# Actual.net
KiCad netlist of a schematic drawn in Altium Designer
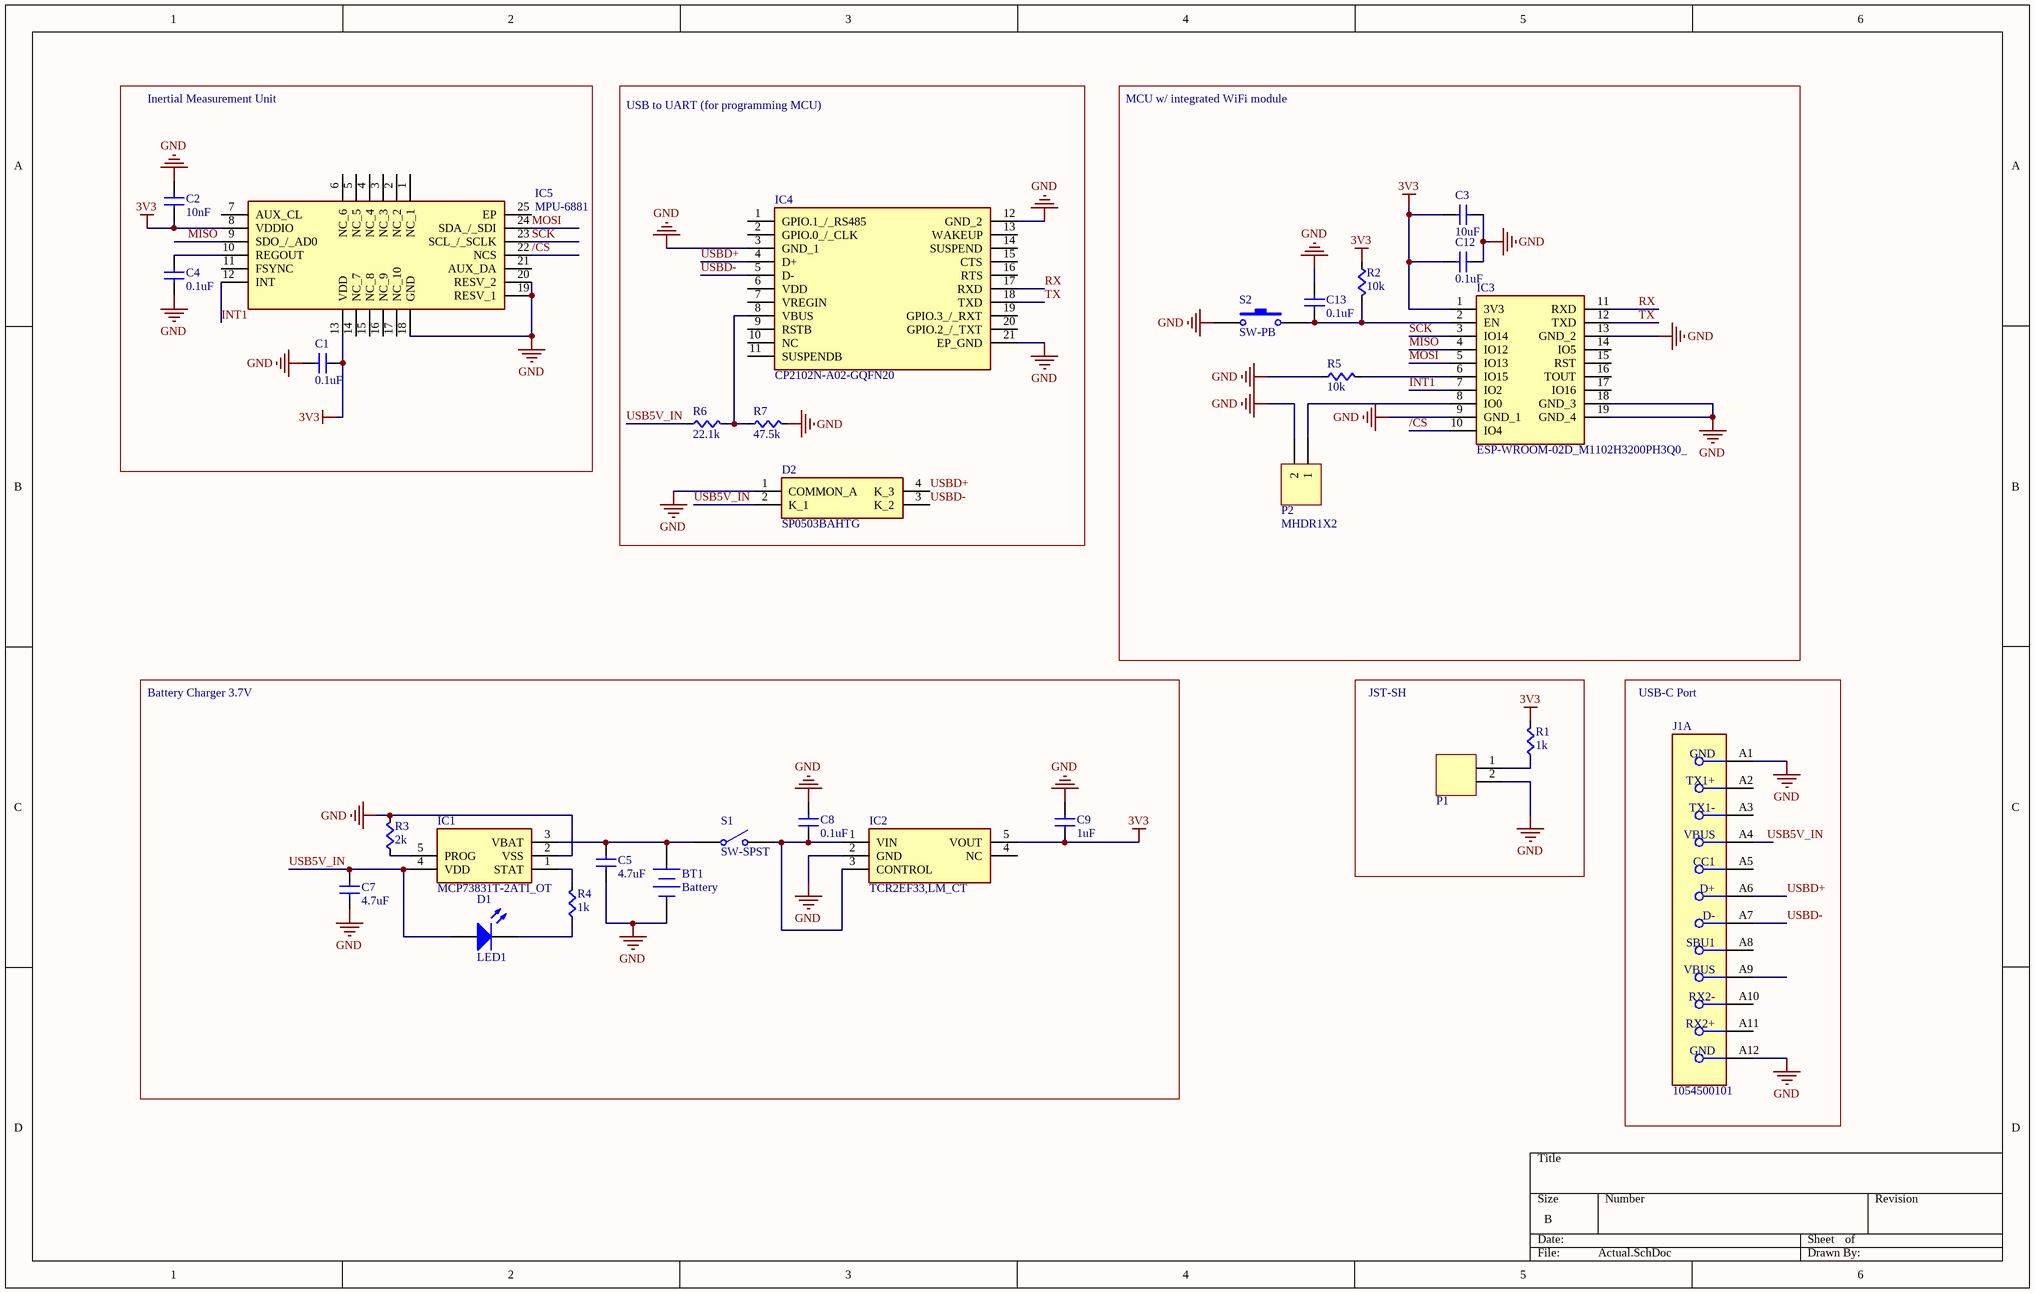
[diagram p0: Actual.SchDoc]

(export (version "E")
  (design (tool "Eeschema 10.0.6"))
  (components
    (comp (ref "BT1")
      (value "Battery")
      (footprint "BAT-2")
      (description "Multicell Battery")
      (fields (field (name "PUBLISHER") "Altium Limited"))
      (libsource (lib "Miscellaneous Devices") (part "Battery"))
    )
    (comp (ref "C1")
      (value "0.1uF")
      (footprint "CAPC0603")
      (fields (field (name "Comment") "Cap"))
      (libsource (lib "Passives") (part "Cap"))
    )
    (comp (ref "C2")
      (value "10nF")
      (footprint "CAPC0603")
      (fields (field (name "Comment") "Cap"))
      (libsource (lib "Passives") (part "Cap"))
    )
    (comp (ref "C3")
      (value "10uF")
      (footprint "CAPC0603")
      (fields (field (name "Comment") "Cap"))
      (libsource (lib "Passives") (part "Cap"))
    )
    (comp (ref "C4")
      (value "0.1uF")
      (footprint "CAPC0603")
      (fields (field (name "Comment") "Cap"))
      (libsource (lib "Passives") (part "Cap"))
    )
    (comp (ref "C5")
      (value "4.7uF")
      (footprint "CAPC0603")
      (fields (field (name "Comment") "Cap"))
      (libsource (lib "Passives") (part "Cap"))
    )
    (comp (ref "C7")
      (value "4.7uF")
      (footprint "CAPC0603")
      (fields (field (name "Comment") "Cap"))
      (libsource (lib "Passives") (part "Cap"))
    )
    (comp (ref "C8")
      (value "0.1uF")
      (footprint "CAPC0603")
      (fields (field (name "Comment") "Cap"))
      (libsource (lib "Passives") (part "Cap"))
    )
    (comp (ref "C9")
      (value "1uF")
      (footprint "CAPC0603")
      (fields (field (name "Comment") "Cap"))
      (libsource (lib "Passives") (part "Cap"))
    )
    (comp (ref "C12")
      (value "0.1uF")
      (footprint "CAPC0603")
      (fields (field (name "Comment") "Cap"))
      (libsource (lib "Passives") (part "Cap"))
    )
    (comp (ref "C13")
      (value "0.1uF")
      (footprint "CAPC0603")
      (fields (field (name "Comment") "Cap"))
      (libsource (lib "Passives") (part "Cap"))
    )
    (comp (ref "D1")
      (value "LED1")
      (footprint "LED-1")
      (description "Typical RED GaAs LED")
      (fields (field (name "PUBLISHER") "Altium Limited"))
      (libsource (lib "Miscellaneous Devices") (part "LED1"))
    )
    (comp (ref "D2")
      (value "SP0503BAHTG")
      (footprint "SamacSys:SP0503BAHTG")
      (description "TVS Diode (Uni-directional)")
      (fields (field (name "MOUSER PART NUMBER") "576-SP0503BAHTG"))
      (libsource (lib "*") (part "SP0503BAHTG"))
    )
    (comp (ref "IC1")
      (value "MCP73831T-2ATI_OT")
      (footprint "SamacSys:SOT95P270X145-5N")
      (description "Integrated Circuit")
      (fields
        (field (name "MOUSER2 PART NUMBER") "579-MCP73831T-2ATIOT")
        (field (name "MANUFACTURER_PART_NUMBER") "MCP73831T-2ATI/OT")
      )
      (libsource (lib "*") (part "MCP73831T-2ATI_OT"))
    )
    (comp (ref "IC2")
      (value "TCR2EF33,LM_CT")
      (footprint "SamacSys:SOT-25")
      (description "Integrated Circuit")
      (fields
        (field (name "MOUSER2 PART NUMBER") "757-TCR2EF33LMCT")
        (field (name "MANUFACTURER_PART_NUMBER") "TCR2EF33,LM(CT")
      )
      (libsource (lib "*") (part "TCR2EF33,LM_CT"))
    )
    (comp (ref "IC3")
      (value "ESP-WROOM-02D_M1102H3200PH3Q0_")
      (footprint "SamacSys:ESPWROOM02DM1102H3200PH3Q0")
      (description "Integrated Circuit")
      (fields
        (field (name "MANUFACTURER_PART_NUMBER") "ESP-WROOM-02D(M1102H3200PH3Q0)")
        (field (name "MOUSER PART NUMBER") "356-ESPWROOM02D(4MB)")
      )
      (libsource (lib "*") (part "ESP-WROOM-02D_M1102H3200PH3Q0_"))
    )
    (comp (ref "IC4")
      (value "CP2102N-A02-GQFN20")
      (footprint "SamacSys:CP2102NA02GQFN20")
      (description "Integrated Circuit")
      (fields (field (name "MOUSER PART NUMBER") "634-CP2102NA02GQFN20"))
      (libsource (lib "*") (part "CP2102N-A02-GQFN20"))
    )
    (comp (ref "IC5")
      (value "MPU-6881")
      (footprint "SamacSys:QFN40P300X300X95-25N-D")
      (description "Integrated Circuit")
      (fields (field (name "MOUSER PART NUMBER") "410-MPU-6881"))
      (libsource (lib "*") (part "MPU-6881"))
    )
    (comp (ref "J1")
      (value "1054500101")
      (footprint "FP-1054500101-MFG")
      (description "CONN RCP USB3.1 TYPEC 24P SMD RA")
      (fields
        (field (name "MANUFACTURER") "Molex")
        (field (name "OCTOPART") "https://octopart.com/105450-0101-molex-68082325")
      )
      (libsource (lib "Altium Content Vault") (part "9808b19ecaf079fb99eed69f0495cd0"))
    )
    (comp (ref "P1")
      (value "2-pin Horz Sherlock")
      (footprint "MOLEX-HDR-1X2-SHERLOCK-HORZ")
      (fields
        (field (name "MANUFACTURER PART NUMBER") "0353630260")
        (field (name "MANUFACTURER") "Molex Inc")
      )
      (libsource (lib "Connectors") (part "MOLEX-HDR-1x2-SHERLOCK_RA"))
    )
    (comp (ref "P2")
      (value "MHDR1X2")
      (footprint "MHDR1X2")
      (description "Header, 2-Pin")
      (fields (field (name "PUBLISHER") "Altium Limited"))
      (libsource (lib "Miscellaneous Connectors") (part "MHDR1X2"))
    )
    (comp (ref "R1")
      (value "1k")
      (footprint "RES0603")
      (fields (field (name "Comment") "Res"))
      (libsource (lib "Passives") (part "Res"))
    )
    (comp (ref "R2")
      (value "10k")
      (footprint "RES0603")
      (fields (field (name "Comment") "Res"))
      (libsource (lib "Passives") (part "Res"))
    )
    (comp (ref "R3")
      (value "2k")
      (footprint "RES0603")
      (fields (field (name "Comment") "Res"))
      (libsource (lib "Passives") (part "Res"))
    )
    (comp (ref "R4")
      (value "1k")
      (footprint "RES0603")
      (fields (field (name "Comment") "Res"))
      (libsource (lib "Passives") (part "Res"))
    )
    (comp (ref "R5")
      (value "10k")
      (footprint "RES0603")
      (fields (field (name "Comment") "Res"))
      (libsource (lib "Passives") (part "Res"))
    )
    (comp (ref "R6")
      (value "22.1k")
      (footprint "RES0603")
      (fields (field (name "Comment") "Res"))
      (libsource (lib "Passives") (part "Res"))
    )
    (comp (ref "R7")
      (value "47.5k")
      (footprint "RES0603")
      (fields (field (name "Comment") "Res"))
      (libsource (lib "Passives") (part "Res"))
    )
    (comp (ref "S1")
      (value "SW-SPST")
      (footprint "SPST-2")
      (description "Single-Pole, Single-Throw Switch")
      (fields (field (name "PUBLISHER") "Altium Limited"))
      (libsource (lib "Miscellaneous Devices") (part "SW-SPST"))
    )
    (comp (ref "S2")
      (value "SW-PB")
      (footprint "SPST-2")
      (description "Switch")
      (fields (field (name "PUBLISHER") "Altium Limited"))
      (libsource (lib "Miscellaneous Devices") (part "SW-PB"))
    )
  )
  (nets
    (net (code "1") (name "/INT1") (class "Default")
      (node (ref "IC3") (pin "7") (pinfunction "IO2_7") (pintype "passive"))
      (node (ref "IC5") (pin "12") (pinfunction "INT_12") (pintype "passive"))
    )
    (net (code "2") (name "/MISO") (class "Default")
      (node (ref "IC3") (pin "4") (pinfunction "IO12_4") (pintype "passive"))
      (node (ref "IC5") (pin "9") (pinfunction "SDO_/_AD0_9") (pintype "passive"))
    )
    (net (code "3") (name "/MOSI") (class "Default")
      (node (ref "IC3") (pin "5") (pinfunction "IO13_5") (pintype "passive"))
      (node (ref "IC5") (pin "24") (pinfunction "SDA_/_SDI_24") (pintype "passive"))
    )
    (net (code "4") (name "/RX") (class "Default")
      (node (ref "IC3") (pin "11") (pinfunction "RXD_11") (pintype "passive"))
      (node (ref "IC4") (pin "17") (pinfunction "RXD_17") (pintype "passive"))
    )
    (net (code "5") (name "/SCK") (class "Default")
      (node (ref "IC3") (pin "3") (pinfunction "IO14_3") (pintype "passive"))
      (node (ref "IC5") (pin "23") (pinfunction "SCL_/_SCLK_23") (pintype "passive"))
    )
    (net (code "6") (name "/TX") (class "Default")
      (node (ref "IC3") (pin "12") (pinfunction "TXD_12") (pintype "passive"))
      (node (ref "IC4") (pin "18") (pinfunction "TXD_18") (pintype "passive"))
    )
    (net (code "7") (name "/USB5V_IN") (class "Default")
      (node (ref "C7") (pin "2") (pinfunction "B_2") (pintype "passive"))
      (node (ref "D1") (pin "1") (pinfunction "A_1") (pintype "passive"))
      (node (ref "D2") (pin "2") (pinfunction "K_1_2") (pintype "passive"))
      (node (ref "IC1") (pin "4") (pinfunction "VDD_4") (pintype "power_in"))
      (node (ref "J1") (pin "A4") (pinfunction "VBUS_A4") (pintype "passive"))
      (node (ref "R6") (pin "2") (pinfunction "B_2") (pintype "passive"))
    )
    (net (code "8") (name "/USBD+") (class "Default")
      (node (ref "D2") (pin "4") (pinfunction "K_3_4") (pintype "passive"))
      (node (ref "IC4") (pin "4") (pinfunction "D+_4") (pintype "passive"))
      (node (ref "J1") (pin "A6") (pinfunction "D+_A6") (pintype "passive"))
    )
    (net (code "9") (name "/USBD-") (class "Default")
      (node (ref "D2") (pin "3") (pinfunction "K_2_3") (pintype "passive"))
      (node (ref "IC4") (pin "5") (pinfunction "D-_5") (pintype "passive"))
      (node (ref "J1") (pin "A7") (pinfunction "D-_A7") (pintype "passive"))
    )
    (net (code "10") (name "/{slash}CS") (class "Default")
      (node (ref "IC3") (pin "10") (pinfunction "IO4_10") (pintype "passive"))
      (node (ref "IC5") (pin "22") (pinfunction "NCS_22") (pintype "passive"))
    )
    (net (code "11") (name "3V3") (class "Default")
      (node (ref "C1") (pin "1") (pinfunction "A_1") (pintype "passive"))
      (node (ref "C12") (pin "2") (pinfunction "B_2") (pintype "passive"))
      (node (ref "C2") (pin "1") (pinfunction "A_1") (pintype "passive"))
      (node (ref "C3") (pin "2") (pinfunction "B_2") (pintype "passive"))
      (node (ref "C9") (pin "1") (pinfunction "A_1") (pintype "passive"))
      (node (ref "IC2") (pin "5") (pinfunction "VOUT_5") (pintype "passive"))
      (node (ref "IC3") (pin "1") (pinfunction "3V3_1") (pintype "passive"))
      (node (ref "IC5") (pin "13") (pinfunction "VDD_13") (pintype "passive"))
      (node (ref "IC5") (pin "8") (pinfunction "VDDIO_8") (pintype "passive"))
      (node (ref "R1") (pin "1") (pinfunction "A_1") (pintype "passive"))
      (node (ref "R2") (pin "2") (pinfunction "B_2") (pintype "passive"))
    )
    (net (code "12") (name "GND") (class "Default")
      (node (ref "BT1") (pin "2") (pinfunction "-_2") (pintype "passive"))
      (node (ref "C1") (pin "2") (pinfunction "B_2") (pintype "passive"))
      (node (ref "C12") (pin "1") (pinfunction "A_1") (pintype "passive"))
      (node (ref "C13") (pin "2") (pinfunction "B_2") (pintype "passive"))
      (node (ref "C2") (pin "2") (pinfunction "B_2") (pintype "passive"))
      (node (ref "C3") (pin "1") (pinfunction "A_1") (pintype "passive"))
      (node (ref "C4") (pin "1") (pinfunction "A_1") (pintype "passive"))
      (node (ref "C5") (pin "1") (pinfunction "A_1") (pintype "passive"))
      (node (ref "C7") (pin "1") (pinfunction "A_1") (pintype "passive"))
      (node (ref "C8") (pin "2") (pinfunction "B_2") (pintype "passive"))
      (node (ref "C9") (pin "2") (pinfunction "B_2") (pintype "passive"))
      (node (ref "D2") (pin "1") (pinfunction "COMMON_A_1") (pintype "passive"))
      (node (ref "IC1") (pin "2") (pinfunction "VSS_2") (pintype "power_in"))
      (node (ref "IC2") (pin "2") (pinfunction "GND_2") (pintype "passive"))
      (node (ref "IC3") (pin "13") (pinfunction "GND_2_13") (pintype "passive"))
      (node (ref "IC3") (pin "18") (pinfunction "GND_3_18") (pintype "passive"))
      (node (ref "IC3") (pin "19") (pinfunction "GND_4_19") (pintype "passive"))
      (node (ref "IC3") (pin "9") (pinfunction "GND_1_9") (pintype "passive"))
      (node (ref "IC4") (pin "12") (pinfunction "GND_2_12") (pintype "passive"))
      (node (ref "IC4") (pin "21") (pinfunction "EP_GND_21") (pintype "passive"))
      (node (ref "IC4") (pin "3") (pinfunction "GND_1_3") (pintype "passive"))
      (node (ref "IC5") (pin "18") (pinfunction "GND_18") (pintype "passive"))
      (node (ref "IC5") (pin "19") (pinfunction "RESV_1_19") (pintype "passive"))
      (node (ref "IC5") (pin "20") (pinfunction "RESV_2_20") (pintype "passive"))
      (node (ref "J1") (pin "A1") (pinfunction "GND_A1") (pintype "passive"))
      (node (ref "J1") (pin "A12") (pinfunction "GND_A12") (pintype "passive"))
      (node (ref "P1") (pin "2") (pinfunction "2_2") (pintype "passive"))
      (node (ref "P2") (pin "2") (pinfunction "2_2") (pintype "passive"))
      (node (ref "R3") (pin "1") (pinfunction "A_1") (pintype "passive"))
      (node (ref "R5") (pin "2") (pinfunction "B_2") (pintype "passive"))
      (node (ref "R7") (pin "1") (pinfunction "A_1") (pintype "passive"))
      (node (ref "S2") (pin "1") (pinfunction "1_1") (pintype "passive"))
    )
    (net (code "13") (name "Net-(BT1-+)") (class "Default")
      (node (ref "BT1") (pin "1") (pinfunction "+_1") (pintype "passive"))
      (node (ref "C5") (pin "2") (pinfunction "B_2") (pintype "passive"))
      (node (ref "IC1") (pin "3") (pinfunction "VBAT_3") (pintype "passive"))
      (node (ref "S1") (pin "1") (pinfunction "COMMON_1") (pintype "passive"))
    )
    (net (code "14") (name "Net-(C4-B)") (class "Default")
      (node (ref "C4") (pin "2") (pinfunction "B_2") (pintype "passive"))
      (node (ref "IC5") (pin "10") (pinfunction "REGOUT_10") (pintype "passive"))
    )
    (net (code "15") (name "Net-(C8-A)") (class "Default")
      (node (ref "C8") (pin "1") (pinfunction "A_1") (pintype "passive"))
      (node (ref "IC2") (pin "1") (pinfunction "VIN_1") (pintype "passive"))
      (node (ref "IC2") (pin "3") (pinfunction "CONTROL_3") (pintype "passive"))
      (node (ref "S1") (pin "2") (pinfunction "NO_2") (pintype "passive"))
    )
    (net (code "16") (name "Net-(C13-A)") (class "Default")
      (node (ref "C13") (pin "1") (pinfunction "A_1") (pintype "passive"))
      (node (ref "IC3") (pin "2") (pinfunction "EN_2") (pintype "passive"))
      (node (ref "R2") (pin "1") (pinfunction "A_1") (pintype "passive"))
      (node (ref "S2") (pin "2") (pinfunction "2_2") (pintype "passive"))
    )
    (net (code "17") (name "Net-(D1-K)") (class "Default")
      (node (ref "D1") (pin "2") (pinfunction "K_2") (pintype "passive"))
      (node (ref "R4") (pin "2") (pinfunction "B_2") (pintype "passive"))
    )
    (net (code "18") (name "Net-(IC1-PROG)") (class "Default")
      (node (ref "IC1") (pin "5") (pinfunction "PROG_5") (pintype "passive"))
      (node (ref "R3") (pin "2") (pinfunction "B_2") (pintype "passive"))
    )
    (net (code "19") (name "Net-(IC1-STAT)") (class "Default")
      (node (ref "IC1") (pin "1") (pinfunction "STAT_1") (pintype "passive"))
      (node (ref "R4") (pin "1") (pinfunction "A_1") (pintype "passive"))
    )
    (net (code "20") (name "Net-(IC3-IO0)") (class "Default")
      (node (ref "IC3") (pin "8") (pinfunction "IO0_8") (pintype "passive"))
      (node (ref "P2") (pin "1") (pinfunction "1_1") (pintype "passive"))
    )
    (net (code "21") (name "Net-(IC3-IO15)") (class "Default")
      (node (ref "IC3") (pin "6") (pinfunction "IO15_6") (pintype "passive"))
      (node (ref "R5") (pin "1") (pinfunction "A_1") (pintype "passive"))
    )
    (net (code "22") (name "Net-(IC4-VBUS)") (class "Default")
      (node (ref "IC4") (pin "8") (pinfunction "VBUS_8") (pintype "passive"))
      (node (ref "R6") (pin "1") (pinfunction "A_1") (pintype "passive"))
      (node (ref "R7") (pin "2") (pinfunction "B_2") (pintype "passive"))
    )
    (net (code "23") (name "Net-(R1-B)") (class "Default")
      (node (ref "P1") (pin "1") (pinfunction "1_1") (pintype "passive"))
      (node (ref "R1") (pin "2") (pinfunction "B_2") (pintype "passive"))
    )
    (net (code "24") (name "unconnected-(IC2-NC-Pad4)") (class "Default")
      (node (ref "IC2") (pin "4") (pinfunction "NC_4") (pintype "passive"))
    )
    (net (code "25") (name "unconnected-(IC3-IO5-Pad14)") (class "Default")
      (node (ref "IC3") (pin "14") (pinfunction "IO5_14") (pintype "passive"))
    )
    (net (code "26") (name "unconnected-(IC3-IO16-Pad17)") (class "Default")
      (node (ref "IC3") (pin "17") (pinfunction "IO16_17") (pintype "passive"))
    )
    (net (code "27") (name "unconnected-(IC3-RST-Pad15)") (class "Default")
      (node (ref "IC3") (pin "15") (pinfunction "RST_15") (pintype "passive"))
    )
    (net (code "28") (name "unconnected-(IC3-TOUT-Pad16)") (class "Default")
      (node (ref "IC3") (pin "16") (pinfunction "TOUT_16") (pintype "passive"))
    )
    (net (code "29") (name "unconnected-(IC4-CTS-Pad15)") (class "Default")
      (node (ref "IC4") (pin "15") (pinfunction "CTS_15") (pintype "passive"))
    )
    (net (code "30") (name "unconnected-(IC4-GPIO.0_{slash}_CLK-Pad2)") (class "Default")
      (node (ref "IC4") (pin "2") (pinfunction "GPIO.0_/_CLK_2") (pintype "passive"))
    )
    (net (code "31") (name "unconnected-(IC4-GPIO.1_{slash}_RS485-Pad1)") (class "Default")
      (node (ref "IC4") (pin "1") (pinfunction "GPIO.1_/_RS485_1") (pintype "passive"))
    )
    (net (code "32") (name "unconnected-(IC4-GPIO.2_{slash}_TXT-Pad20)") (class "Default")
      (node (ref "IC4") (pin "20") (pinfunction "GPIO.2_/_TXT_20") (pintype "passive"))
    )
    (net (code "33") (name "unconnected-(IC4-GPIO.3_{slash}_RXT-Pad19)") (class "Default")
      (node (ref "IC4") (pin "19") (pinfunction "GPIO.3_/_RXT_19") (pintype "passive"))
    )
    (net (code "34") (name "unconnected-(IC4-NC-Pad10)") (class "Default")
      (node (ref "IC4") (pin "10") (pinfunction "NC_10") (pintype "passive"))
    )
    (net (code "35") (name "unconnected-(IC4-RSTB-Pad9)") (class "Default")
      (node (ref "IC4") (pin "9") (pinfunction "RSTB_9") (pintype "passive"))
    )
    (net (code "36") (name "unconnected-(IC4-RTS-Pad16)") (class "Default")
      (node (ref "IC4") (pin "16") (pinfunction "RTS_16") (pintype "passive"))
    )
    (net (code "37") (name "unconnected-(IC4-SUSPEND-Pad14)") (class "Default")
      (node (ref "IC4") (pin "14") (pinfunction "SUSPEND_14") (pintype "passive"))
    )
    (net (code "38") (name "unconnected-(IC4-SUSPENDB-Pad11)") (class "Default")
      (node (ref "IC4") (pin "11") (pinfunction "SUSPENDB_11") (pintype "passive"))
    )
    (net (code "39") (name "unconnected-(IC4-VDD-Pad6)") (class "Default")
      (node (ref "IC4") (pin "6") (pinfunction "VDD_6") (pintype "passive"))
    )
    (net (code "40") (name "unconnected-(IC4-VREGIN-Pad7)") (class "Default")
      (node (ref "IC4") (pin "7") (pinfunction "VREGIN_7") (pintype "passive"))
    )
    (net (code "41") (name "unconnected-(IC4-WAKEUP-Pad13)") (class "Default")
      (node (ref "IC4") (pin "13") (pinfunction "WAKEUP_13") (pintype "passive"))
    )
    (net (code "42") (name "unconnected-(IC5-AUX_CL-Pad7)") (class "Default")
      (node (ref "IC5") (pin "7") (pinfunction "AUX_CL_7") (pintype "passive"))
    )
    (net (code "43") (name "unconnected-(IC5-AUX_DA-Pad21)") (class "Default")
      (node (ref "IC5") (pin "21") (pinfunction "AUX_DA_21") (pintype "passive"))
    )
    (net (code "44") (name "unconnected-(IC5-EP-Pad25)") (class "Default")
      (node (ref "IC5") (pin "25") (pinfunction "EP_25") (pintype "passive"))
    )
    (net (code "45") (name "unconnected-(IC5-FSYNC-Pad11)") (class "Default")
      (node (ref "IC5") (pin "11") (pinfunction "FSYNC_11") (pintype "passive"))
    )
    (net (code "46") (name "unconnected-(IC5-NC_1-Pad1)") (class "Default")
      (node (ref "IC5") (pin "1") (pinfunction "NC_1_1") (pintype "passive"))
    )
    (net (code "47") (name "unconnected-(IC5-NC_2-Pad2)") (class "Default")
      (node (ref "IC5") (pin "2") (pinfunction "NC_2_2") (pintype "passive"))
    )
    (net (code "48") (name "unconnected-(IC5-NC_3-Pad3)") (class "Default")
      (node (ref "IC5") (pin "3") (pinfunction "NC_3_3") (pintype "passive"))
    )
    (net (code "49") (name "unconnected-(IC5-NC_4-Pad4)") (class "Default")
      (node (ref "IC5") (pin "4") (pinfunction "NC_4_4") (pintype "passive"))
    )
    (net (code "50") (name "unconnected-(IC5-NC_5-Pad5)") (class "Default")
      (node (ref "IC5") (pin "5") (pinfunction "NC_5_5") (pintype "passive"))
    )
    (net (code "51") (name "unconnected-(IC5-NC_6-Pad6)") (class "Default")
      (node (ref "IC5") (pin "6") (pinfunction "NC_6_6") (pintype "passive"))
    )
    (net (code "52") (name "unconnected-(IC5-NC_7-Pad14)") (class "Default")
      (node (ref "IC5") (pin "14") (pinfunction "NC_7_14") (pintype "passive"))
    )
    (net (code "53") (name "unconnected-(IC5-NC_8-Pad15)") (class "Default")
      (node (ref "IC5") (pin "15") (pinfunction "NC_8_15") (pintype "passive"))
    )
    (net (code "54") (name "unconnected-(IC5-NC_9-Pad16)") (class "Default")
      (node (ref "IC5") (pin "16") (pinfunction "NC_9_16") (pintype "passive"))
    )
    (net (code "55") (name "unconnected-(IC5-NC_10-Pad17)") (class "Default")
      (node (ref "IC5") (pin "17") (pinfunction "NC_10_17") (pintype "passive"))
    )
    (net (code "56") (name "unconnected-(J1A-CC1-PadA5)") (class "Default")
      (node (ref "J1") (pin "A5") (pinfunction "CC1_A5") (pintype "passive"))
    )
    (net (code "57") (name "unconnected-(J1A-RX2+-PadA11)") (class "Default")
      (node (ref "J1") (pin "A11") (pinfunction "RX2+_A11") (pintype "passive"))
    )
    (net (code "58") (name "unconnected-(J1A-RX2--PadA10)") (class "Default")
      (node (ref "J1") (pin "A10") (pinfunction "RX2-_A10") (pintype "passive"))
    )
    (net (code "59") (name "unconnected-(J1A-SBU1-PadA8)") (class "Default")
      (node (ref "J1") (pin "A8") (pinfunction "SBU1_A8") (pintype "passive"))
    )
    (net (code "60") (name "unconnected-(J1A-TX1+-PadA2)") (class "Default")
      (node (ref "J1") (pin "A2") (pinfunction "TX1+_A2") (pintype "passive"))
    )
    (net (code "61") (name "unconnected-(J1A-TX1--PadA3)") (class "Default")
      (node (ref "J1") (pin "A3") (pinfunction "TX1-_A3") (pintype "passive"))
    )
    (net (code "62") (name "unconnected-(J1A-VBUS-PadA9)") (class "Default")
      (node (ref "J1") (pin "A9") (pinfunction "VBUS_A9") (pintype "passive"))
    )
  )
)
